# EEG.net
KiCad netlist of a schematic drawn in Altium Designer
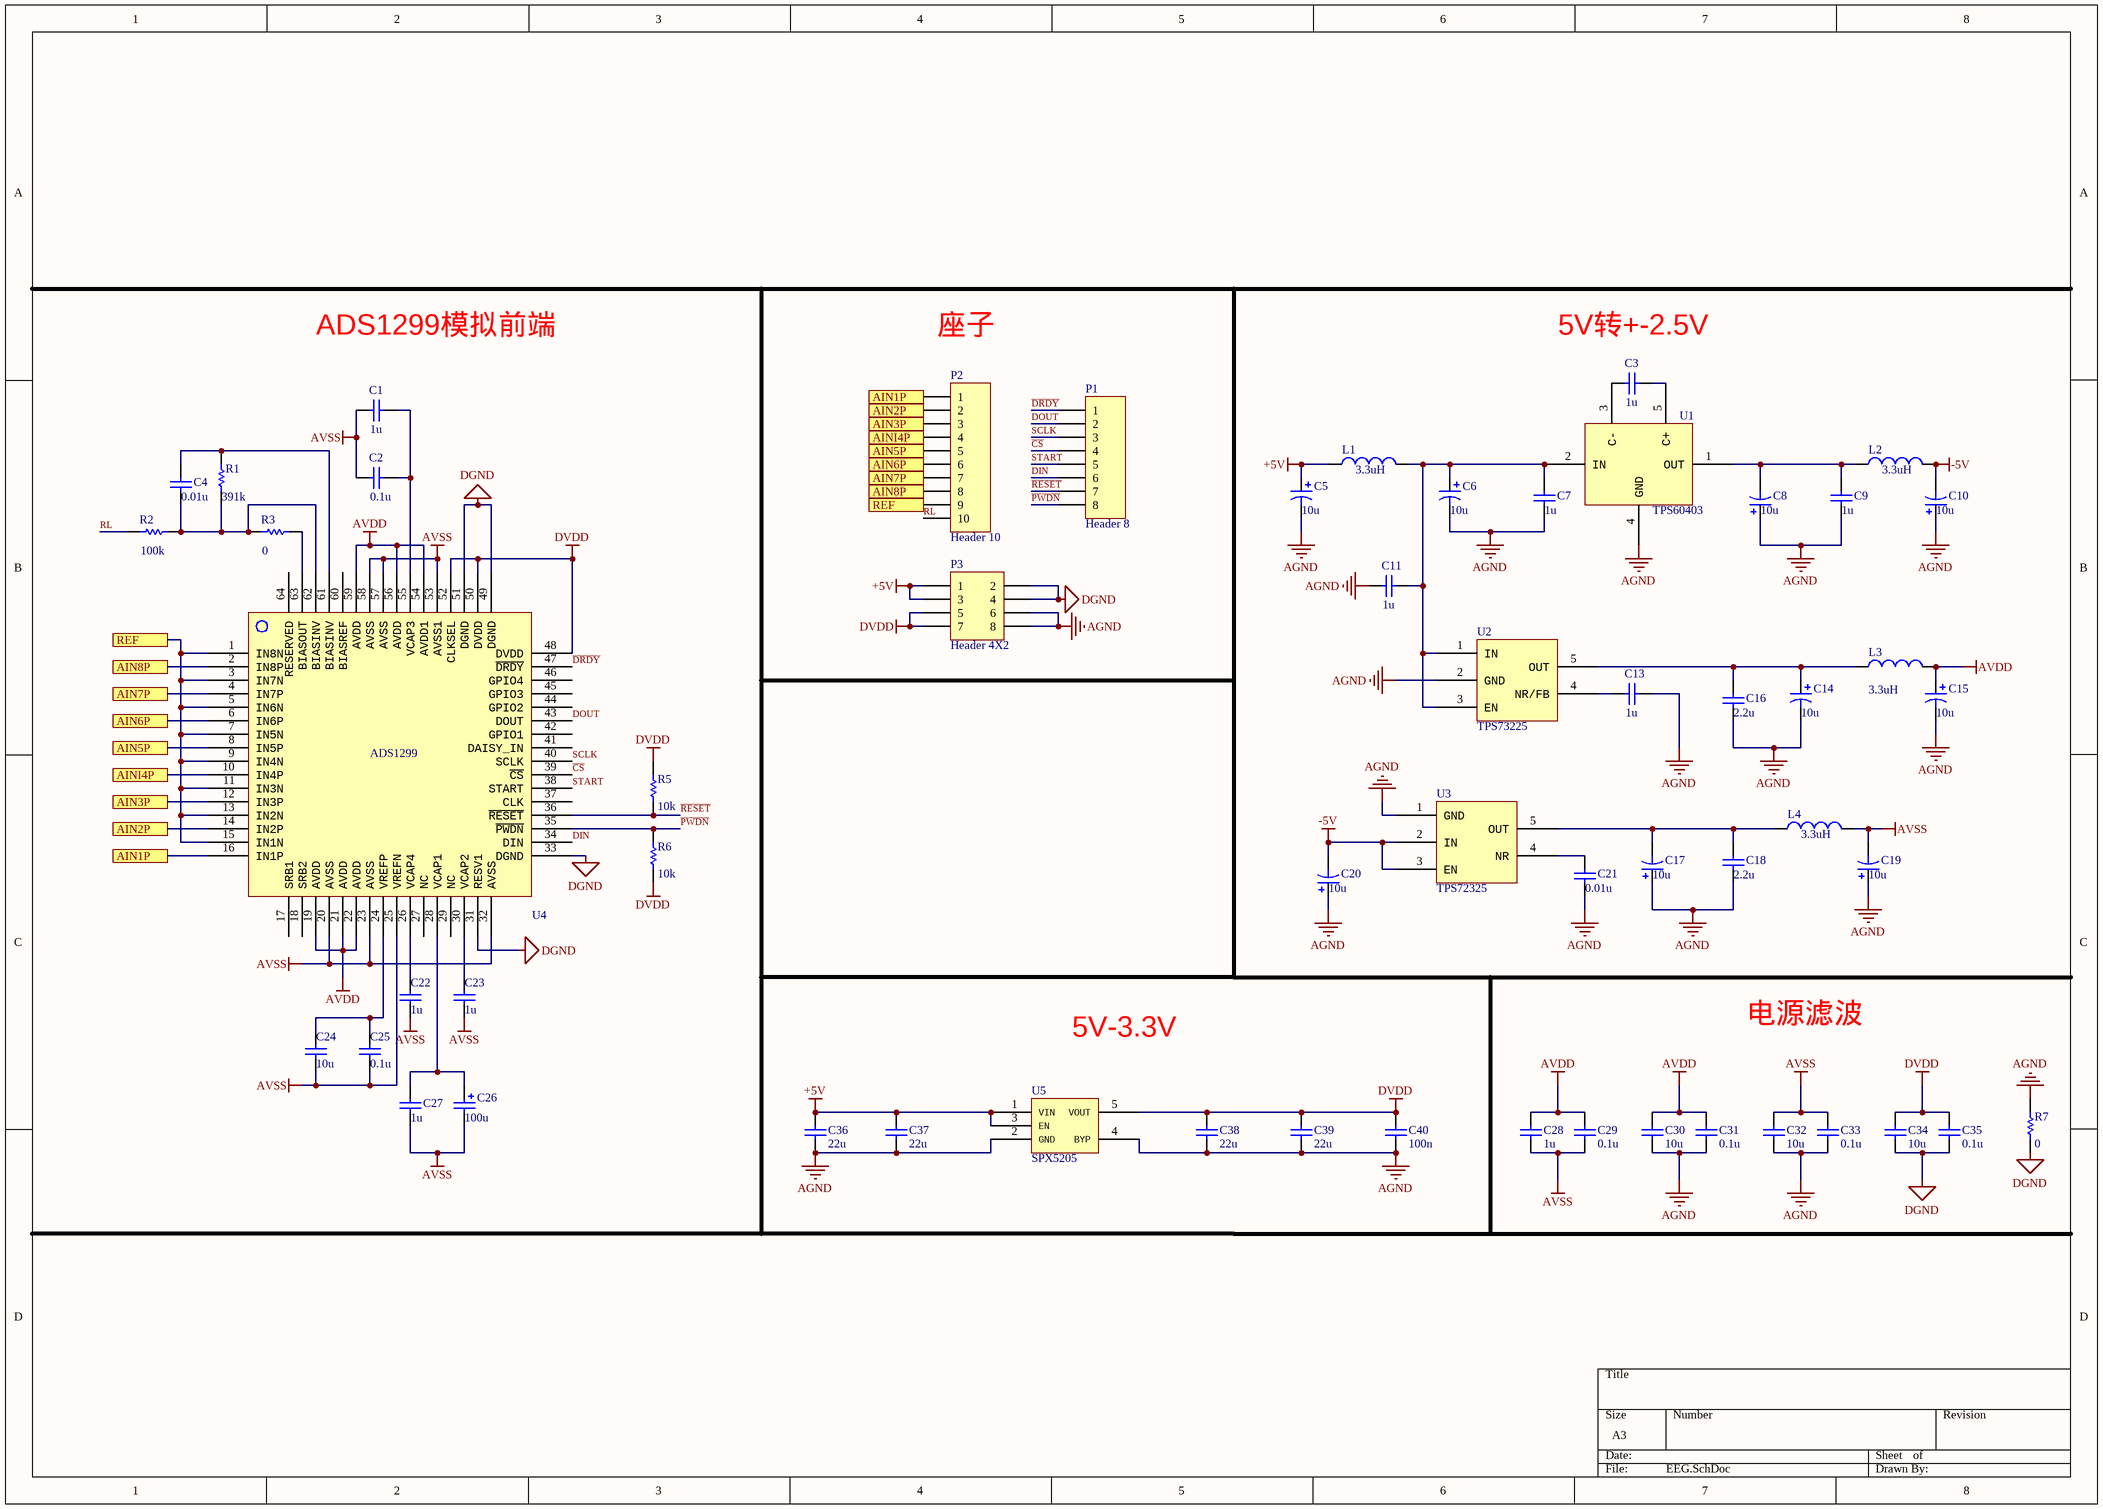
[diagram p0: EEG.SchDoc]

(export (version "E")
  (design (tool "Eeschema 10.0.6"))
  (components
    (comp (ref "C1")
      (value "1u")
      (footprint "0603-1")
      (description "Capacitor")
      (fields (field (name "Comment") "Cap") (field (name "PUBLISHER") "Altium Limited"))
      (libsource (lib "Miscellaneous Devices") (part "Cap"))
    )
    (comp (ref "C2")
      (value "0.1u")
      (footprint "0603-1")
      (description "Capacitor")
      (fields (field (name "Comment") "Cap") (field (name "PUBLISHER") "Altium Limited"))
      (libsource (lib "Miscellaneous Devices") (part "Cap"))
    )
    (comp (ref "C3")
      (value "1u")
      (footprint "0603-1")
      (description "Capacitor")
      (fields (field (name "Comment") "Cap") (field (name "PUBLISHER") "Altium Limited"))
      (libsource (lib "Miscellaneous Devices") (part "Cap"))
    )
    (comp (ref "C4")
      (value "0.01u")
      (footprint "0603-1")
      (description "Capacitor")
      (fields (field (name "Comment") "Cap") (field (name "PUBLISHER") "Altium Limited"))
      (libsource (lib "Miscellaneous Devices") (part "Cap"))
    )
    (comp (ref "C5")
      (value "10u")
      (footprint "0603-1")
      (description "Polarized Capacitor (Radial)")
      (fields (field (name "Comment") "Cap Pol1") (field (name "PUBLISHER") "Altium Limited"))
      (libsource (lib "Miscellaneous Devices") (part "Cap Pol1"))
    )
    (comp (ref "C6")
      (value "10u")
      (footprint "0603-1")
      (description "Polarized Capacitor (Radial)")
      (fields (field (name "Comment") "Cap Pol1") (field (name "PUBLISHER") "Altium Limited"))
      (libsource (lib "Miscellaneous Devices") (part "Cap Pol1"))
    )
    (comp (ref "C7")
      (value "1u")
      (footprint "0603-1")
      (description "Capacitor")
      (fields (field (name "Comment") "Cap") (field (name "PUBLISHER") "Altium Limited"))
      (libsource (lib "Miscellaneous Devices") (part "Cap"))
    )
    (comp (ref "C8")
      (value "10u")
      (footprint "0603-1")
      (description "Polarized Capacitor (Radial)")
      (fields (field (name "Comment") "Cap Pol1") (field (name "PUBLISHER") "Altium Limited"))
      (libsource (lib "Miscellaneous Devices") (part "Cap Pol1"))
    )
    (comp (ref "C9")
      (value "1u")
      (footprint "0603-1")
      (description "Capacitor")
      (fields (field (name "Comment") "Cap") (field (name "PUBLISHER") "Altium Limited"))
      (libsource (lib "Miscellaneous Devices") (part "Cap"))
    )
    (comp (ref "C10")
      (value "10u")
      (footprint "0603-1")
      (description "Polarized Capacitor (Radial)")
      (fields (field (name "Comment") "Cap Pol1") (field (name "PUBLISHER") "Altium Limited"))
      (libsource (lib "Miscellaneous Devices") (part "Cap Pol1"))
    )
    (comp (ref "C11")
      (value "1u")
      (footprint "0603-1")
      (description "Capacitor")
      (fields (field (name "Comment") "Cap") (field (name "PUBLISHER") "Altium Limited"))
      (libsource (lib "Miscellaneous Devices") (part "Cap"))
    )
    (comp (ref "C13")
      (value "1u")
      (footprint "0603-1")
      (description "Capacitor")
      (fields (field (name "Comment") "Cap") (field (name "PUBLISHER") "Altium Limited"))
      (libsource (lib "Miscellaneous Devices") (part "Cap"))
    )
    (comp (ref "C14")
      (value "10u")
      (footprint "0603-1")
      (description "Polarized Capacitor (Radial)")
      (fields (field (name "Comment") "Cap Pol1") (field (name "PUBLISHER") "Altium Limited"))
      (libsource (lib "Miscellaneous Devices") (part "Cap Pol1"))
    )
    (comp (ref "C15")
      (value "10u")
      (footprint "0603-1")
      (description "Polarized Capacitor (Radial)")
      (fields (field (name "Comment") "Cap Pol1") (field (name "PUBLISHER") "Altium Limited"))
      (libsource (lib "Miscellaneous Devices") (part "Cap Pol1"))
    )
    (comp (ref "C16")
      (value "2.2u")
      (footprint "0603-1")
      (description "Capacitor")
      (fields (field (name "Comment") "Cap") (field (name "PUBLISHER") "Altium Limited"))
      (libsource (lib "Miscellaneous Devices") (part "Cap"))
    )
    (comp (ref "C17")
      (value "10u")
      (footprint "0603-1")
      (description "Polarized Capacitor (Radial)")
      (fields (field (name "Comment") "Cap Pol1") (field (name "PUBLISHER") "Altium Limited"))
      (libsource (lib "Miscellaneous Devices") (part "Cap Pol1"))
    )
    (comp (ref "C18")
      (value "2.2u")
      (footprint "0603-1")
      (description "Capacitor")
      (fields (field (name "Comment") "Cap") (field (name "PUBLISHER") "Altium Limited"))
      (libsource (lib "Miscellaneous Devices") (part "Cap"))
    )
    (comp (ref "C19")
      (value "10u")
      (footprint "0603-1")
      (description "Polarized Capacitor (Radial)")
      (fields (field (name "Comment") "Cap Pol1") (field (name "PUBLISHER") "Altium Limited"))
      (libsource (lib "Miscellaneous Devices") (part "Cap Pol1"))
    )
    (comp (ref "C20")
      (value "10u")
      (footprint "0603-1")
      (description "Polarized Capacitor (Radial)")
      (fields (field (name "Comment") "Cap Pol1") (field (name "PUBLISHER") "Altium Limited"))
      (libsource (lib "Miscellaneous Devices") (part "Cap Pol1"))
    )
    (comp (ref "C21")
      (value "0.01u")
      (footprint "0603-1")
      (description "Capacitor")
      (fields (field (name "Comment") "Cap") (field (name "PUBLISHER") "Altium Limited"))
      (libsource (lib "Miscellaneous Devices") (part "Cap"))
    )
    (comp (ref "C22")
      (value "1u")
      (footprint "0603-1")
      (description "Capacitor")
      (fields (field (name "Comment") "Cap") (field (name "PUBLISHER") "Altium Limited"))
      (libsource (lib "Miscellaneous Devices") (part "Cap"))
    )
    (comp (ref "C23")
      (value "1u")
      (footprint "0603-1")
      (description "Capacitor")
      (fields (field (name "Comment") "Cap") (field (name "PUBLISHER") "Altium Limited"))
      (libsource (lib "Miscellaneous Devices") (part "Cap"))
    )
    (comp (ref "C24")
      (value "10u")
      (footprint "0603-1")
      (description "Capacitor")
      (fields (field (name "Comment") "Cap") (field (name "PUBLISHER") "Altium Limited"))
      (libsource (lib "Miscellaneous Devices") (part "Cap"))
    )
    (comp (ref "C25")
      (value "0.1u")
      (footprint "0603-1")
      (description "Capacitor")
      (fields (field (name "Comment") "Cap") (field (name "PUBLISHER") "Altium Limited"))
      (libsource (lib "Miscellaneous Devices") (part "Cap"))
    )
    (comp (ref "C26")
      (value "100u")
      (footprint "0603-1")
      (description "Polarized Capacitor (Axial)")
      (fields (field (name "Comment") "Cap Pol2") (field (name "PUBLISHER") "Altium Limited"))
      (libsource (lib "Miscellaneous Devices") (part "Cap Pol2"))
    )
    (comp (ref "C27")
      (value "1u")
      (footprint "0603-1")
      (description "Capacitor")
      (fields (field (name "Comment") "Cap") (field (name "PUBLISHER") "Altium Limited"))
      (libsource (lib "Miscellaneous Devices") (part "Cap"))
    )
    (comp (ref "C28")
      (value "1u")
      (footprint "0603-1")
      (description "Capacitor")
      (fields (field (name "Comment") "Cap") (field (name "PUBLISHER") "Altium Limited"))
      (libsource (lib "Miscellaneous Devices") (part "Cap"))
    )
    (comp (ref "C29")
      (value "0.1u")
      (footprint "0603-1")
      (description "Capacitor")
      (fields (field (name "Comment") "Cap") (field (name "PUBLISHER") "Altium Limited"))
      (libsource (lib "Miscellaneous Devices") (part "Cap"))
    )
    (comp (ref "C30")
      (value "10u")
      (footprint "0603-1")
      (description "Capacitor")
      (fields (field (name "Comment") "Cap") (field (name "PUBLISHER") "Altium Limited"))
      (libsource (lib "Miscellaneous Devices") (part "Cap"))
    )
    (comp (ref "C31")
      (value "0.1u")
      (footprint "0603-1")
      (description "Capacitor")
      (fields (field (name "Comment") "Cap") (field (name "PUBLISHER") "Altium Limited"))
      (libsource (lib "Miscellaneous Devices") (part "Cap"))
    )
    (comp (ref "C32")
      (value "10u")
      (footprint "0603-1")
      (description "Capacitor")
      (fields (field (name "Comment") "Cap") (field (name "PUBLISHER") "Altium Limited"))
      (libsource (lib "Miscellaneous Devices") (part "Cap"))
    )
    (comp (ref "C33")
      (value "0.1u")
      (footprint "0603-1")
      (description "Capacitor")
      (fields (field (name "Comment") "Cap") (field (name "PUBLISHER") "Altium Limited"))
      (libsource (lib "Miscellaneous Devices") (part "Cap"))
    )
    (comp (ref "C34")
      (value "10u")
      (footprint "0603-1")
      (description "Capacitor")
      (fields (field (name "Comment") "Cap") (field (name "PUBLISHER") "Altium Limited"))
      (libsource (lib "Miscellaneous Devices") (part "Cap"))
    )
    (comp (ref "C35")
      (value "0.1u")
      (footprint "0603-1")
      (description "Capacitor")
      (fields (field (name "Comment") "Cap") (field (name "PUBLISHER") "Altium Limited"))
      (libsource (lib "Miscellaneous Devices") (part "Cap"))
    )
    (comp (ref "C36")
      (value "22u")
      (footprint "0603-1")
      (description "Capacitor")
      (fields (field (name "Comment") "Cap") (field (name "PUBLISHER") "Altium Limited"))
      (libsource (lib "Miscellaneous Devices") (part "Cap"))
    )
    (comp (ref "C37")
      (value "22u")
      (footprint "0603-1")
      (description "Capacitor")
      (fields (field (name "Comment") "Cap") (field (name "PUBLISHER") "Altium Limited"))
      (libsource (lib "Miscellaneous Devices") (part "Cap"))
    )
    (comp (ref "C38")
      (value "22u")
      (footprint "0603-1")
      (description "Capacitor")
      (fields (field (name "Comment") "Cap") (field (name "PUBLISHER") "Altium Limited"))
      (libsource (lib "Miscellaneous Devices") (part "Cap"))
    )
    (comp (ref "C39")
      (value "22u")
      (footprint "0603-1")
      (description "Capacitor")
      (fields (field (name "Comment") "Cap") (field (name "PUBLISHER") "Altium Limited"))
      (libsource (lib "Miscellaneous Devices") (part "Cap"))
    )
    (comp (ref "C40")
      (value "100n")
      (footprint "0603-1")
      (description "Capacitor")
      (fields (field (name "Comment") "Cap") (field (name "PUBLISHER") "Altium Limited"))
      (libsource (lib "Miscellaneous Devices") (part "Cap"))
    )
    (comp (ref "L1")
      (value "3.3uH")
      (footprint "L-SMD-7")
      (description "Inductor")
      (fields (field (name "PUBLISHER") "Altium Limited"))
      (libsource (lib "Miscellaneous Devices") (part "Inductor"))
    )
    (comp (ref "L2")
      (value "3.3uH")
      (footprint "L-SMD-7")
      (description "Inductor")
      (fields (field (name "PUBLISHER") "Altium Limited"))
      (libsource (lib "Miscellaneous Devices") (part "Inductor"))
    )
    (comp (ref "L3")
      (value "3.3uH")
      (footprint "L-SMD-7")
      (description "Inductor")
      (fields (field (name "PUBLISHER") "Altium Limited"))
      (libsource (lib "Miscellaneous Devices") (part "Inductor"))
    )
    (comp (ref "L4")
      (value "3.3uH")
      (footprint "L-SMD-7")
      (description "Inductor")
      (fields (field (name "PUBLISHER") "Altium Limited"))
      (libsource (lib "Miscellaneous Devices") (part "Inductor"))
    )
    (comp (ref "P1")
      (value "Header 8")
      (footprint "HDR1X8")
      (description "Header, 8-Pin")
      (fields (field (name "PUBLISHER") "Altium Limited"))
      (libsource (lib "Miscellaneous Connectors") (part "Header 8"))
    )
    (comp (ref "P2")
      (value "Header 10")
      (footprint "HDR1X10")
      (description "Header, 10-Pin")
      (fields (field (name "PUBLISHER") "Altium Limited"))
      (libsource (lib "Miscellaneous Connectors") (part "Header 10"))
    )
    (comp (ref "P3")
      (value "Header 4X2")
      (footprint "HDR2X4")
      (description "Header, 4-Pin, Dual row")
      (fields (field (name "PUBLISHER") "Altium Limited"))
      (libsource (lib "Miscellaneous Connectors") (part "Header 4X2"))
    )
    (comp (ref "R1")
      (value "391k")
      (footprint "0603-1")
      (description "Resistor")
      (fields (field (name "Comment") "Res1") (field (name "PUBLISHER") "Altium Limited"))
      (libsource (lib "Miscellaneous Devices") (part "Res1"))
    )
    (comp (ref "R2")
      (value "100k")
      (footprint "0603-1")
      (description "Resistor")
      (fields (field (name "Comment") "Res1") (field (name "PUBLISHER") "Altium Limited"))
      (libsource (lib "Miscellaneous Devices") (part "Res1"))
    )
    (comp (ref "R3")
      (value "0")
      (footprint "0603-1")
      (description "Resistor")
      (fields (field (name "Comment") "Res1") (field (name "PUBLISHER") "Altium Limited"))
      (libsource (lib "Miscellaneous Devices") (part "Res1"))
    )
    (comp (ref "R5")
      (value "10k")
      (footprint "0603-1")
      (description "Resistor")
      (fields (field (name "Comment") "Res1") (field (name "PUBLISHER") "Altium Limited"))
      (libsource (lib "Miscellaneous Devices") (part "Res1"))
    )
    (comp (ref "R6")
      (value "10k")
      (footprint "0603-1")
      (description "Resistor")
      (fields (field (name "Comment") "Res1") (field (name "PUBLISHER") "Altium Limited"))
      (libsource (lib "Miscellaneous Devices") (part "Res1"))
    )
    (comp (ref "R7")
      (value "0")
      (footprint "0603-1")
      (description "Resistor")
      (fields (field (name "Comment") "Res1") (field (name "PUBLISHER") "Altium Limited"))
      (libsource (lib "Miscellaneous Devices") (part "Res1"))
    )
    (comp (ref "U1")
      (value "TPS60403")
      (footprint "tps723/732/60403")
      (libsource (lib "ads1299") (part "TPS60403"))
    )
    (comp (ref "U2")
      (value "TPS73225")
      (footprint "tps723/732/60403")
      (libsource (lib "ads1299") (part "TPS73225"))
    )
    (comp (ref "U3")
      (value "TPS72325")
      (footprint "tps723/732/60403")
      (libsource (lib "ads1299") (part "TPS72325"))
    )
    (comp (ref "U4") (value "ADS1299") (footprint "ADS1299") (libsource (lib "ads1299") (part "ADS1299")))
    (comp (ref "U5") (value "SPX5205") (footprint "SPX5205") (libsource (lib "EEG") (part "SPX5205")))
  )
  (nets
    (net (code "1") (name "+5V") (class "Default")
      (node (ref "C36") (pin "1") (pinfunction "1_1") (pintype "passive"))
      (node (ref "C37") (pin "1") (pinfunction "1_1") (pintype "passive"))
      (node (ref "C5") (pin "1") (pinfunction "1_1") (pintype "passive"))
      (node (ref "L1") (pin "1") (pinfunction "1_1") (pintype "passive"))
      (node (ref "P3") (pin "1") (pinfunction "1_1") (pintype "passive"))
      (node (ref "P3") (pin "3") (pinfunction "3_3") (pintype "passive"))
      (node (ref "U5") (pin "1") (pinfunction "VIN_1") (pintype "passive"))
      (node (ref "U5") (pin "3") (pinfunction "EN_3") (pintype "passive"))
    )
    (net (code "2") (name "-5V") (class "Default")
      (node (ref "C10") (pin "2") (pinfunction "2_2") (pintype "passive"))
      (node (ref "C20") (pin "2") (pinfunction "2_2") (pintype "passive"))
      (node (ref "L2") (pin "2") (pinfunction "2_2") (pintype "passive"))
      (node (ref "U3") (pin "2") (pinfunction "IN_2") (pintype "passive"))
      (node (ref "U3") (pin "3") (pinfunction "EN_3") (pintype "passive"))
    )
    (net (code "3") (name "/AIN1P") (class "Default")
      (node (ref "P2") (pin "1") (pinfunction "1_1") (pintype "passive"))
      (node (ref "U4") (pin "16") (pinfunction "IN1P_16") (pintype "passive"))
    )
    (net (code "4") (name "/AIN2P") (class "Default")
      (node (ref "P2") (pin "2") (pinfunction "2_2") (pintype "passive"))
      (node (ref "U4") (pin "14") (pinfunction "IN2P_14") (pintype "passive"))
    )
    (net (code "5") (name "/AIN3P") (class "Default")
      (node (ref "P2") (pin "3") (pinfunction "3_3") (pintype "passive"))
      (node (ref "U4") (pin "12") (pinfunction "IN3P_12") (pintype "passive"))
    )
    (net (code "6") (name "/AIN5P") (class "Default")
      (node (ref "P2") (pin "5") (pinfunction "5_5") (pintype "passive"))
      (node (ref "U4") (pin "8") (pinfunction "IN5P_8") (pintype "passive"))
    )
    (net (code "7") (name "/AIN6P") (class "Default")
      (node (ref "P2") (pin "6") (pinfunction "6_6") (pintype "passive"))
      (node (ref "U4") (pin "6") (pinfunction "IN6P_6") (pintype "passive"))
    )
    (net (code "8") (name "/AIN7P") (class "Default")
      (node (ref "P2") (pin "7") (pinfunction "7_7") (pintype "passive"))
      (node (ref "U4") (pin "4") (pinfunction "IN7P_4") (pintype "passive"))
    )
    (net (code "9") (name "/AIN8P") (class "Default")
      (node (ref "P2") (pin "8") (pinfunction "8_8") (pintype "passive"))
      (node (ref "U4") (pin "2") (pinfunction "IN8P_2") (pintype "passive"))
    )
    (net (code "10") (name "/AINI4P") (class "Default")
      (node (ref "P2") (pin "4") (pinfunction "4_4") (pintype "passive"))
      (node (ref "U4") (pin "10") (pinfunction "IN4P_10") (pintype "passive"))
    )
    (net (code "11") (name "/DIN") (class "Default")
      (node (ref "P1") (pin "6") (pinfunction "6_6") (pintype "passive"))
      (node (ref "U4") (pin "34") (pinfunction "DIN_34") (pintype "passive"))
    )
    (net (code "12") (name "/DOUT") (class "Default")
      (node (ref "P1") (pin "2") (pinfunction "2_2") (pintype "passive"))
      (node (ref "U4") (pin "43") (pinfunction "DOUT_43") (pintype "passive"))
    )
    (net (code "13") (name "/REF") (class "Default")
      (node (ref "P2") (pin "9") (pinfunction "9_9") (pintype "passive"))
      (node (ref "U4") (pin "1") (pinfunction "IN8N_1") (pintype "passive"))
      (node (ref "U4") (pin "11") (pinfunction "IN3N_11") (pintype "passive"))
      (node (ref "U4") (pin "13") (pinfunction "IN2N_13") (pintype "passive"))
      (node (ref "U4") (pin "15") (pinfunction "IN1N_15") (pintype "passive"))
      (node (ref "U4") (pin "3") (pinfunction "IN7N_3") (pintype "passive"))
      (node (ref "U4") (pin "5") (pinfunction "IN6N_5") (pintype "passive"))
      (node (ref "U4") (pin "7") (pinfunction "IN5N_7") (pintype "passive"))
      (node (ref "U4") (pin "9") (pinfunction "IN4N_9") (pintype "passive"))
    )
    (net (code "14") (name "/RL") (class "Default")
      (node (ref "P2") (pin "10") (pinfunction "10_10") (pintype "passive"))
      (node (ref "R2") (pin "1") (pinfunction "1_1") (pintype "passive"))
    )
    (net (code "15") (name "/SCLK") (class "Default")
      (node (ref "P1") (pin "3") (pinfunction "3_3") (pintype "passive"))
      (node (ref "U4") (pin "40") (pinfunction "SCLK_40") (pintype "passive"))
    )
    (net (code "16") (name "/START") (class "Default")
      (node (ref "P1") (pin "5") (pinfunction "5_5") (pintype "passive"))
      (node (ref "U4") (pin "38") (pinfunction "START_38") (pintype "passive"))
    )
    (net (code "17") (name "/~{CS}") (class "Default")
      (node (ref "P1") (pin "4") (pinfunction "4_4") (pintype "passive"))
      (node (ref "U4") (pin "39") (pinfunction "~{CS}_39") (pintype "passive"))
    )
    (net (code "18") (name "/~{DRDY}") (class "Default")
      (node (ref "P1") (pin "1") (pinfunction "1_1") (pintype "passive"))
      (node (ref "U4") (pin "47") (pinfunction "~{DRDY}_47") (pintype "passive"))
    )
    (net (code "19") (name "/~{PWDN}") (class "Default")
      (node (ref "P1") (pin "8") (pinfunction "8_8") (pintype "passive"))
      (node (ref "R6") (pin "2") (pinfunction "2_2") (pintype "passive"))
      (node (ref "U4") (pin "35") (pinfunction "~{PWDN}_35") (pintype "passive"))
    )
    (net (code "20") (name "/~{RESET}") (class "Default")
      (node (ref "P1") (pin "7") (pinfunction "7_7") (pintype "passive"))
      (node (ref "R5") (pin "1") (pinfunction "1_1") (pintype "passive"))
      (node (ref "U4") (pin "36") (pinfunction "~{RESET}_36") (pintype "passive"))
    )
    (net (code "21") (name "AGND") (class "Default")
      (node (ref "C10") (pin "1") (pinfunction "1_1") (pintype "passive"))
      (node (ref "C11") (pin "1") (pinfunction "1_1") (pintype "passive"))
      (node (ref "C13") (pin "2") (pinfunction "2_2") (pintype "passive"))
      (node (ref "C14") (pin "2") (pinfunction "2_2") (pintype "passive"))
      (node (ref "C15") (pin "2") (pinfunction "2_2") (pintype "passive"))
      (node (ref "C16") (pin "1") (pinfunction "1_1") (pintype "passive"))
      (node (ref "C17") (pin "1") (pinfunction "1_1") (pintype "passive"))
      (node (ref "C18") (pin "1") (pinfunction "1_1") (pintype "passive"))
      (node (ref "C19") (pin "1") (pinfunction "1_1") (pintype "passive"))
      (node (ref "C20") (pin "1") (pinfunction "1_1") (pintype "passive"))
      (node (ref "C21") (pin "1") (pinfunction "1_1") (pintype "passive"))
      (node (ref "C30") (pin "2") (pinfunction "2_2") (pintype "passive"))
      (node (ref "C31") (pin "2") (pinfunction "2_2") (pintype "passive"))
      (node (ref "C32") (pin "2") (pinfunction "2_2") (pintype "passive"))
      (node (ref "C33") (pin "2") (pinfunction "2_2") (pintype "passive"))
      (node (ref "C36") (pin "2") (pinfunction "2_2") (pintype "passive"))
      (node (ref "C37") (pin "2") (pinfunction "2_2") (pintype "passive"))
      (node (ref "C38") (pin "2") (pinfunction "2_2") (pintype "passive"))
      (node (ref "C39") (pin "2") (pinfunction "2_2") (pintype "passive"))
      (node (ref "C40") (pin "2") (pinfunction "2_2") (pintype "passive"))
      (node (ref "C5") (pin "2") (pinfunction "2_2") (pintype "passive"))
      (node (ref "C6") (pin "2") (pinfunction "2_2") (pintype "passive"))
      (node (ref "C7") (pin "1") (pinfunction "1_1") (pintype "passive"))
      (node (ref "C8") (pin "1") (pinfunction "1_1") (pintype "passive"))
      (node (ref "C9") (pin "1") (pinfunction "1_1") (pintype "passive"))
      (node (ref "P3") (pin "6") (pinfunction "6_6") (pintype "passive"))
      (node (ref "P3") (pin "8") (pinfunction "8_8") (pintype "passive"))
      (node (ref "R7") (pin "2") (pinfunction "2_2") (pintype "passive"))
      (node (ref "U1") (pin "4") (pinfunction "GND_4") (pintype "passive"))
      (node (ref "U2") (pin "2") (pinfunction "GND_2") (pintype "passive"))
      (node (ref "U3") (pin "1") (pinfunction "GND_1") (pintype "passive"))
      (node (ref "U5") (pin "2") (pinfunction "GND_2") (pintype "passive"))
      (node (ref "U5") (pin "4") (pinfunction "BYP_4") (pintype "passive"))
    )
    (net (code "22") (name "AVDD") (class "Default")
      (node (ref "C15") (pin "1") (pinfunction "1_1") (pintype "passive"))
      (node (ref "C28") (pin "1") (pinfunction "1_1") (pintype "passive"))
      (node (ref "C29") (pin "1") (pinfunction "1_1") (pintype "passive"))
      (node (ref "C30") (pin "1") (pinfunction "1_1") (pintype "passive"))
      (node (ref "C31") (pin "1") (pinfunction "1_1") (pintype "passive"))
      (node (ref "L3") (pin "2") (pinfunction "2_2") (pintype "passive"))
      (node (ref "U4") (pin "19") (pinfunction "AVDD_19") (pintype "passive"))
      (node (ref "U4") (pin "21") (pinfunction "AVDD_21") (pintype "passive"))
      (node (ref "U4") (pin "22") (pinfunction "AVDD_22") (pintype "passive"))
      (node (ref "U4") (pin "54") (pinfunction "AVDD1_54") (pintype "passive"))
      (node (ref "U4") (pin "56") (pinfunction "AVDD_56") (pintype "passive"))
      (node (ref "U4") (pin "59") (pinfunction "AVDD_59") (pintype "passive"))
    )
    (net (code "23") (name "AVSS") (class "Default")
      (node (ref "C1") (pin "1") (pinfunction "1_1") (pintype "passive"))
      (node (ref "C19") (pin "2") (pinfunction "2_2") (pintype "passive"))
      (node (ref "C2") (pin "1") (pinfunction "1_1") (pintype "passive"))
      (node (ref "C22") (pin "1") (pinfunction "1_1") (pintype "passive"))
      (node (ref "C23") (pin "1") (pinfunction "1_1") (pintype "passive"))
      (node (ref "C24") (pin "1") (pinfunction "1_1") (pintype "passive"))
      (node (ref "C25") (pin "1") (pinfunction "1_1") (pintype "passive"))
      (node (ref "C26") (pin "2") (pinfunction "2_2") (pintype "passive"))
      (node (ref "C27") (pin "1") (pinfunction "1_1") (pintype "passive"))
      (node (ref "C28") (pin "2") (pinfunction "2_2") (pintype "passive"))
      (node (ref "C29") (pin "2") (pinfunction "2_2") (pintype "passive"))
      (node (ref "C32") (pin "1") (pinfunction "1_1") (pintype "passive"))
      (node (ref "C33") (pin "1") (pinfunction "1_1") (pintype "passive"))
      (node (ref "L4") (pin "2") (pinfunction "2_2") (pintype "passive"))
      (node (ref "U4") (pin "20") (pinfunction "AVSS_20") (pintype "passive"))
      (node (ref "U4") (pin "23") (pinfunction "AVSS_23") (pintype "passive"))
      (node (ref "U4") (pin "25") (pinfunction "VREFN_25") (pintype "passive"))
      (node (ref "U4") (pin "32") (pinfunction "AVSS_32") (pintype "passive"))
      (node (ref "U4") (pin "53") (pinfunction "AVSS1_53") (pintype "passive"))
      (node (ref "U4") (pin "57") (pinfunction "AVSS_57") (pintype "passive"))
      (node (ref "U4") (pin "58") (pinfunction "AVSS_58") (pintype "passive"))
    )
    (net (code "24") (name "DGND") (class "Default")
      (node (ref "C34") (pin "2") (pinfunction "2_2") (pintype "passive"))
      (node (ref "C35") (pin "2") (pinfunction "2_2") (pintype "passive"))
      (node (ref "P3") (pin "2") (pinfunction "2_2") (pintype "passive"))
      (node (ref "P3") (pin "4") (pinfunction "4_4") (pintype "passive"))
      (node (ref "R7") (pin "1") (pinfunction "1_1") (pintype "passive"))
      (node (ref "U4") (pin "31") (pinfunction "RESV1_31") (pintype "passive"))
      (node (ref "U4") (pin "33") (pinfunction "DGND_33") (pintype "passive"))
      (node (ref "U4") (pin "49") (pinfunction "DGND_49") (pintype "passive"))
      (node (ref "U4") (pin "51") (pinfunction "DGND_51") (pintype "passive"))
    )
    (net (code "25") (name "DVDD") (class "Default")
      (node (ref "C34") (pin "1") (pinfunction "1_1") (pintype "passive"))
      (node (ref "C35") (pin "1") (pinfunction "1_1") (pintype "passive"))
      (node (ref "C38") (pin "1") (pinfunction "1_1") (pintype "passive"))
      (node (ref "C39") (pin "1") (pinfunction "1_1") (pintype "passive"))
      (node (ref "C40") (pin "1") (pinfunction "1_1") (pintype "passive"))
      (node (ref "P3") (pin "5") (pinfunction "5_5") (pintype "passive"))
      (node (ref "P3") (pin "7") (pinfunction "7_7") (pintype "passive"))
      (node (ref "R5") (pin "2") (pinfunction "2_2") (pintype "passive"))
      (node (ref "R6") (pin "1") (pinfunction "1_1") (pintype "passive"))
      (node (ref "U4") (pin "48") (pinfunction "DVDD_48") (pintype "passive"))
      (node (ref "U4") (pin "50") (pinfunction "DVDD_50") (pintype "passive"))
      (node (ref "U4") (pin "52") (pinfunction "CLKSEL_52") (pintype "passive"))
      (node (ref "U5") (pin "5") (pinfunction "VOUT_5") (pintype "passive"))
    )
    (net (code "26") (name "Net-(C4-Pad1)") (class "Default")
      (node (ref "C4") (pin "1") (pinfunction "1_1") (pintype "passive"))
      (node (ref "R1") (pin "1") (pinfunction "1_1") (pintype "passive"))
      (node (ref "R2") (pin "2") (pinfunction "2_2") (pintype "passive"))
      (node (ref "R3") (pin "1") (pinfunction "1_1") (pintype "passive"))
      (node (ref "U4") (pin "62") (pinfunction "BIASINV_62") (pintype "passive"))
    )
    (net (code "27") (name "Net-(C4-Pad2)") (class "Default")
      (node (ref "C4") (pin "2") (pinfunction "2_2") (pintype "passive"))
      (node (ref "R1") (pin "2") (pinfunction "2_2") (pintype "passive"))
      (node (ref "U4") (pin "61") (pinfunction "BIASINV_61") (pintype "passive"))
    )
    (net (code "28") (name "Net-(U1-C+)") (class "Default")
      (node (ref "C3") (pin "2") (pinfunction "2_2") (pintype "passive"))
      (node (ref "U1") (pin "5") (pinfunction "C+_5") (pintype "passive"))
    )
    (net (code "29") (name "Net-(U1-C-)") (class "Default")
      (node (ref "C3") (pin "1") (pinfunction "1_1") (pintype "passive"))
      (node (ref "U1") (pin "3") (pinfunction "C-_3") (pintype "passive"))
    )
    (net (code "30") (name "Net-(U1-IN)") (class "Default")
      (node (ref "C11") (pin "2") (pinfunction "2_2") (pintype "passive"))
      (node (ref "C6") (pin "1") (pinfunction "1_1") (pintype "passive"))
      (node (ref "C7") (pin "2") (pinfunction "2_2") (pintype "passive"))
      (node (ref "L1") (pin "2") (pinfunction "2_2") (pintype "passive"))
      (node (ref "U1") (pin "2") (pinfunction "IN_2") (pintype "passive"))
      (node (ref "U2") (pin "1") (pinfunction "IN_1") (pintype "passive"))
      (node (ref "U2") (pin "3") (pinfunction "EN_3") (pintype "passive"))
    )
    (net (code "31") (name "Net-(U1-OUT)") (class "Default")
      (node (ref "C8") (pin "2") (pinfunction "2_2") (pintype "passive"))
      (node (ref "C9") (pin "2") (pinfunction "2_2") (pintype "passive"))
      (node (ref "L2") (pin "1") (pinfunction "1_1") (pintype "passive"))
      (node (ref "U1") (pin "1") (pinfunction "OUT_1") (pintype "passive"))
    )
    (net (code "32") (name "Net-(U2-NR{slash}FB)") (class "Default")
      (node (ref "C13") (pin "1") (pinfunction "1_1") (pintype "passive"))
      (node (ref "U2") (pin "4") (pinfunction "NR/FB_4") (pintype "passive"))
    )
    (net (code "33") (name "Net-(U2-OUT)") (class "Default")
      (node (ref "C14") (pin "1") (pinfunction "1_1") (pintype "passive"))
      (node (ref "C16") (pin "2") (pinfunction "2_2") (pintype "passive"))
      (node (ref "L3") (pin "1") (pinfunction "1_1") (pintype "passive"))
      (node (ref "U2") (pin "5") (pinfunction "OUT_5") (pintype "passive"))
    )
    (net (code "34") (name "Net-(U3-NR)") (class "Default")
      (node (ref "C21") (pin "2") (pinfunction "2_2") (pintype "passive"))
      (node (ref "U3") (pin "4") (pinfunction "NR_4") (pintype "passive"))
    )
    (net (code "35") (name "Net-(U3-OUT)") (class "Default")
      (node (ref "C17") (pin "2") (pinfunction "2_2") (pintype "passive"))
      (node (ref "C18") (pin "2") (pinfunction "2_2") (pintype "passive"))
      (node (ref "L4") (pin "1") (pinfunction "1_1") (pintype "passive"))
      (node (ref "U3") (pin "5") (pinfunction "OUT_5") (pintype "passive"))
    )
    (net (code "36") (name "Net-(U4-BIASOUT)") (class "Default")
      (node (ref "R3") (pin "2") (pinfunction "2_2") (pintype "passive"))
      (node (ref "U4") (pin "63") (pinfunction "BIASOUT_63") (pintype "passive"))
    )
    (net (code "37") (name "Net-(U4-VCAP1)") (class "Default")
      (node (ref "C26") (pin "1") (pinfunction "1_1") (pintype "passive"))
      (node (ref "C27") (pin "2") (pinfunction "2_2") (pintype "passive"))
      (node (ref "U4") (pin "28") (pinfunction "VCAP1_28") (pintype "passive"))
    )
    (net (code "38") (name "Net-(U4-VCAP2)") (class "Default")
      (node (ref "C23") (pin "2") (pinfunction "2_2") (pintype "passive"))
      (node (ref "U4") (pin "30") (pinfunction "VCAP2_30") (pintype "passive"))
    )
    (net (code "39") (name "Net-(U4-VCAP3)") (class "Default")
      (node (ref "C1") (pin "2") (pinfunction "2_2") (pintype "passive"))
      (node (ref "C2") (pin "2") (pinfunction "2_2") (pintype "passive"))
      (node (ref "U4") (pin "55") (pinfunction "VCAP3_55") (pintype "passive"))
    )
    (net (code "40") (name "Net-(U4-VCAP4)") (class "Default")
      (node (ref "C22") (pin "2") (pinfunction "2_2") (pintype "passive"))
      (node (ref "U4") (pin "26") (pinfunction "VCAP4_26") (pintype "passive"))
    )
    (net (code "41") (name "Net-(U4-VREFP)") (class "Default")
      (node (ref "C24") (pin "2") (pinfunction "2_2") (pintype "passive"))
      (node (ref "C25") (pin "2") (pinfunction "2_2") (pintype "passive"))
      (node (ref "U4") (pin "24") (pinfunction "VREFP_24") (pintype "passive"))
    )
    (net (code "42") (name "unconnected-(U4-BIASREF-Pad60)") (class "Default")
      (node (ref "U4") (pin "60") (pinfunction "BIASREF_60") (pintype "passive"))
    )
    (net (code "43") (name "unconnected-(U4-CLK-Pad37)") (class "Default")
      (node (ref "U4") (pin "37") (pinfunction "CLK_37") (pintype "passive"))
    )
    (net (code "44") (name "unconnected-(U4-DAISY_IN-Pad41)") (class "Default")
      (node (ref "U4") (pin "41") (pinfunction "DAISY_IN_41") (pintype "passive"))
    )
    (net (code "45") (name "unconnected-(U4-GPIO1-Pad42)") (class "Default")
      (node (ref "U4") (pin "42") (pinfunction "GPIO1_42") (pintype "passive"))
    )
    (net (code "46") (name "unconnected-(U4-GPIO2-Pad44)") (class "Default")
      (node (ref "U4") (pin "44") (pinfunction "GPIO2_44") (pintype "passive"))
    )
    (net (code "47") (name "unconnected-(U4-GPIO3-Pad45)") (class "Default")
      (node (ref "U4") (pin "45") (pinfunction "GPIO3_45") (pintype "passive"))
    )
    (net (code "48") (name "unconnected-(U4-GPIO4-Pad46)") (class "Default")
      (node (ref "U4") (pin "46") (pinfunction "GPIO4_46") (pintype "passive"))
    )
    (net (code "49") (name "unconnected-(U4-NC-Pad27)") (class "Default")
      (node (ref "U4") (pin "27") (pinfunction "NC_27") (pintype "passive"))
    )
    (net (code "50") (name "unconnected-(U4-NC-Pad29)") (class "Default")
      (node (ref "U4") (pin "29") (pinfunction "NC_29") (pintype "passive"))
    )
    (net (code "51") (name "unconnected-(U4-RESERVED-Pad64)") (class "Default")
      (node (ref "U4") (pin "64") (pinfunction "RESERVED_64") (pintype "passive"))
    )
    (net (code "52") (name "unconnected-(U4-SRB1-Pad17)") (class "Default")
      (node (ref "U4") (pin "17") (pinfunction "SRB1_17") (pintype "passive"))
    )
    (net (code "53") (name "unconnected-(U4-SRB2-Pad18)") (class "Default")
      (node (ref "U4") (pin "18") (pinfunction "SRB2_18") (pintype "passive"))
    )
  )
)
